# SingleEffect.net
KiCad netlist of a schematic drawn in EasyEDA Pro
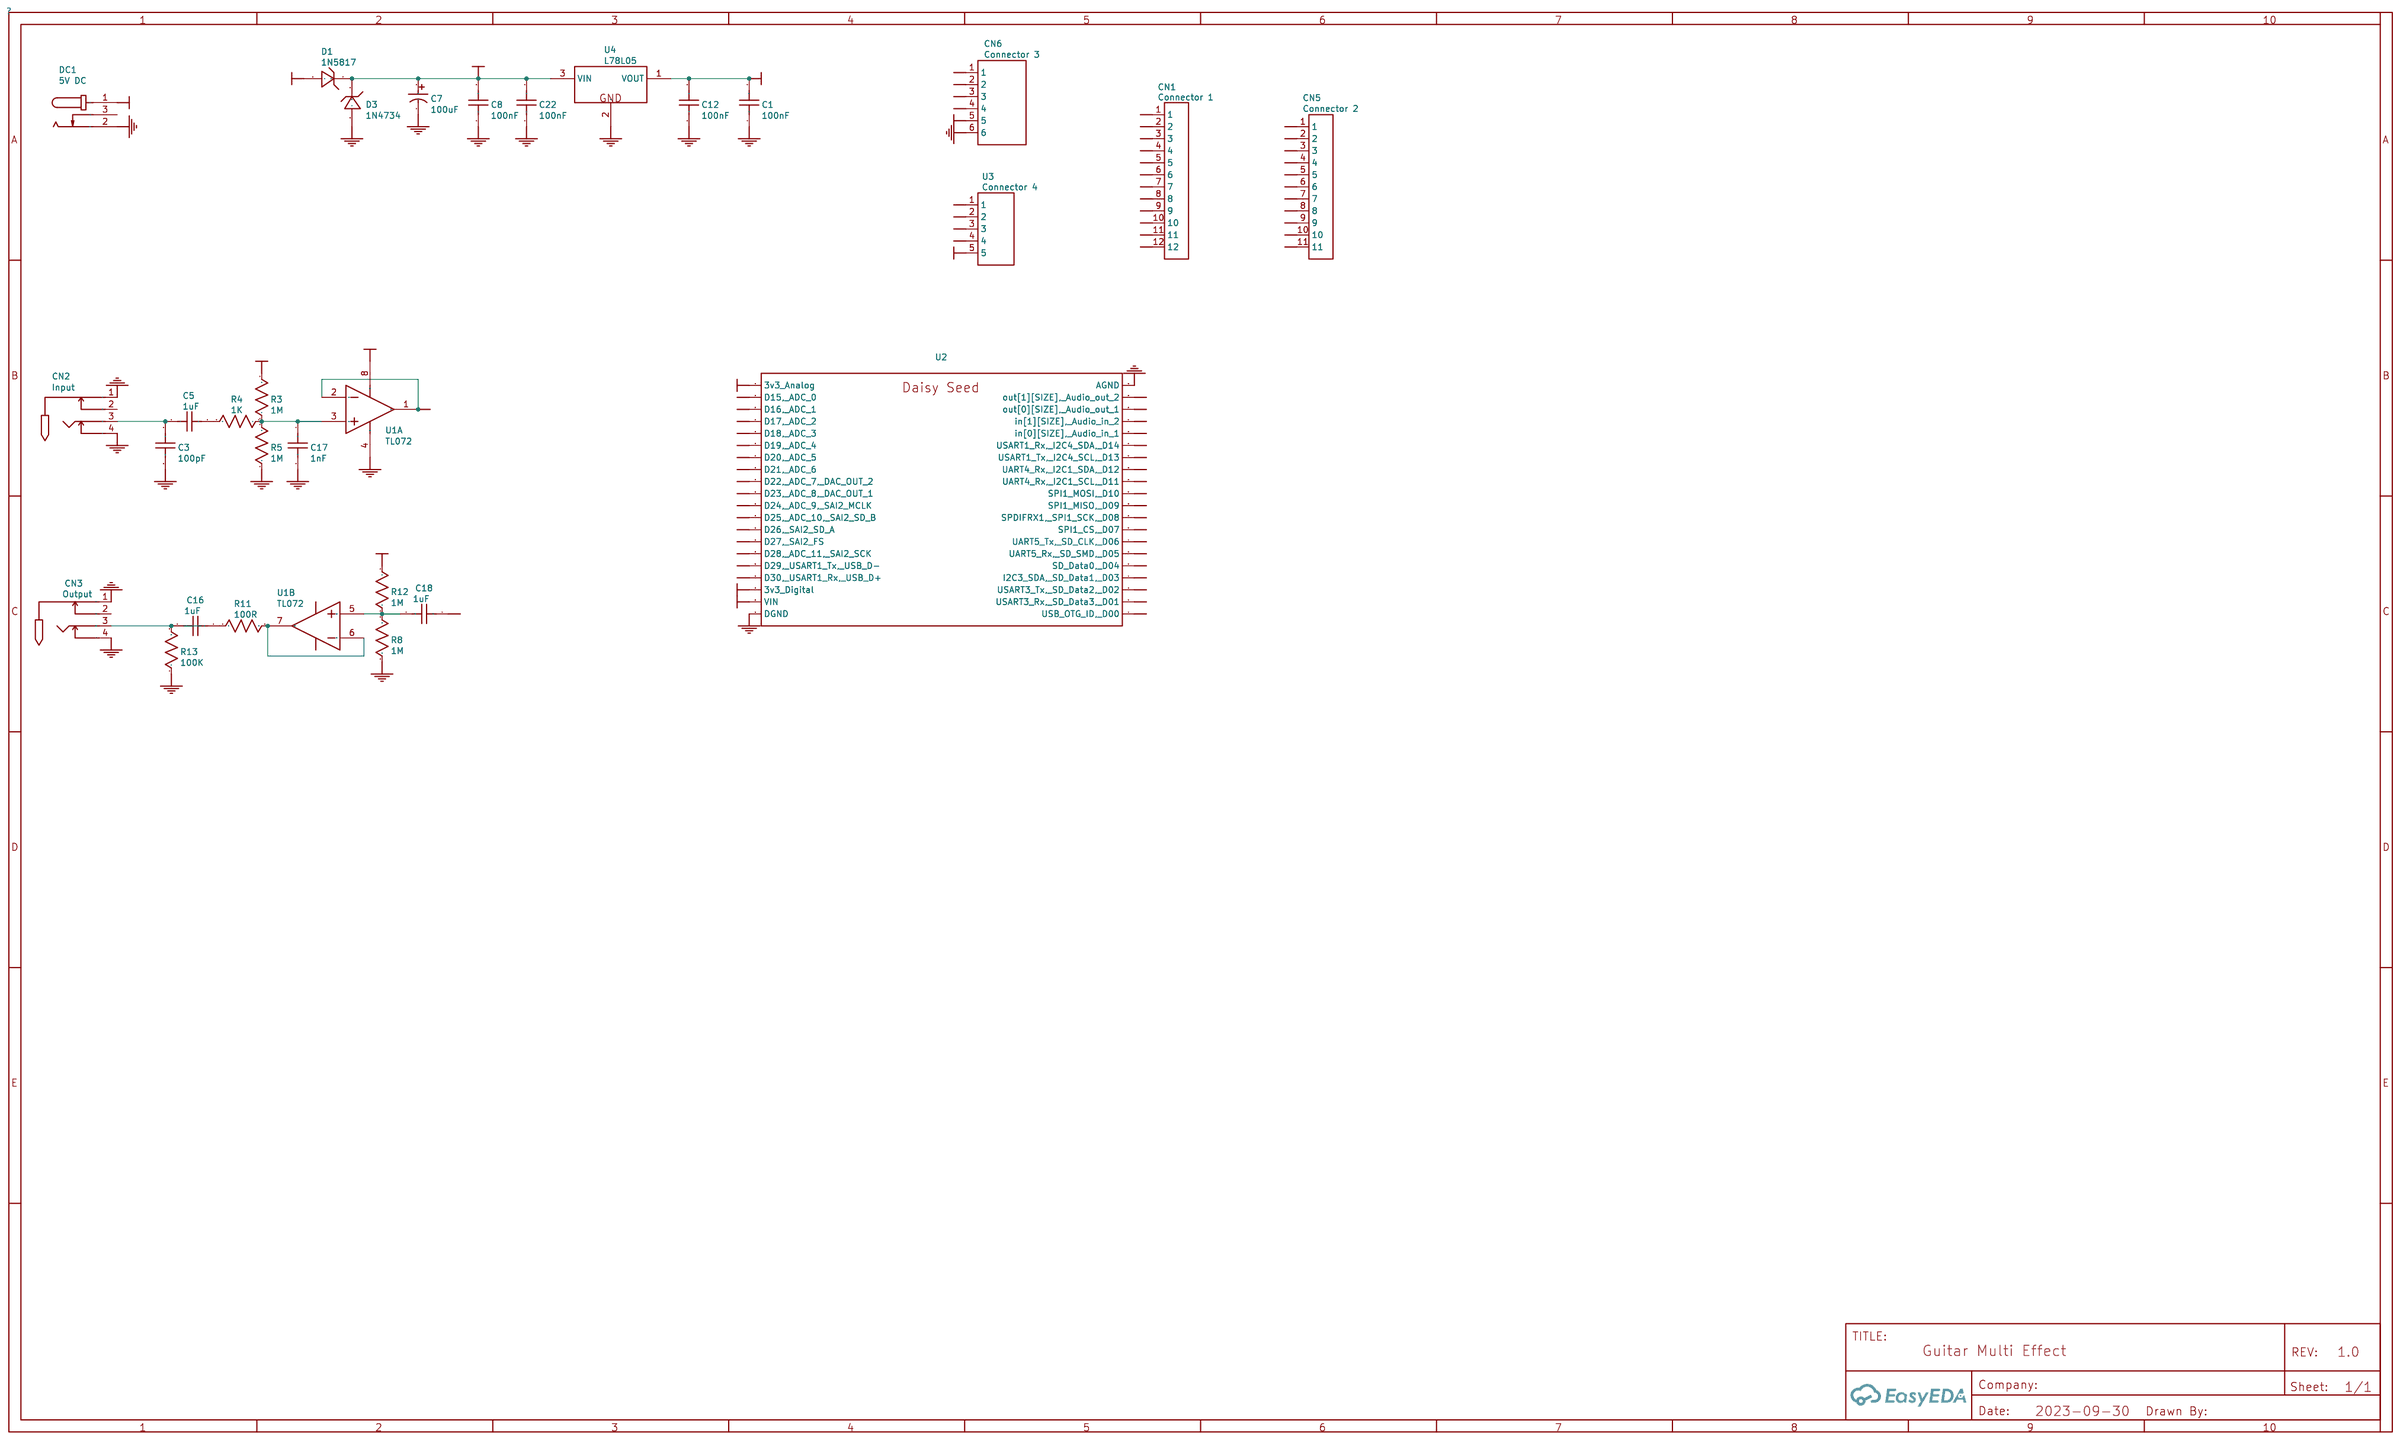
[diagram p0: schematic sheet]

(export (version "E")
  (design (tool "Eeschema 10.0.6"))
  (components
    (comp (ref "C1")
      (value "100nF")
      (footprint "easyedapro:CAP-TH_L8.0-W4.0-P5.00-D0.7")
      (fields
        (field (name "Manufacturer Part") "R08B1B102KN0B0S0N0")
        (field (name "Manufacturer") "STE(松田)")
        (field (name "Contributor") "LCSC")
      )
      (libsource (lib "easyedapro") (part "100nF"))
    )
    (comp (ref "C3")
      (value "100pF")
      (footprint "easyedapro:CAP-TH_L8.0-W4.0-P5.00-D0.7")
      (fields
        (field (name "Manufacturer Part") "R08B1B102KN0B0S0N0")
        (field (name "Manufacturer") "STE(松田)")
        (field (name "Contributor") "LCSC")
      )
      (libsource (lib "easyedapro") (part "100pF"))
    )
    (comp (ref "C5")
      (value "1uF")
      (footprint "easyedapro:CAP-TH_L8.0-W4.0-P5.00-D0.7")
      (fields
        (field (name "Manufacturer Part") "R08B1B102KN0B0S0N0")
        (field (name "Manufacturer") "STE(松田)")
        (field (name "Contributor") "LCSC")
      )
      (libsource (lib "easyedapro") (part "1uF"))
    )
    (comp (ref "C7")
      (value "100uF")
      (footprint "easyedapro:CAP-TH_BD5.0-P2.00-D0.8-FD")
      (fields
        (field (name "Manufacturer Part") "KM475M050D11RR0VH2FP0")
        (field (name "Manufacturer") "CX(承兴)")
      )
      (libsource (lib "easyedapro") (part "100uF"))
    )
    (comp (ref "C8")
      (value "100nF")
      (footprint "easyedapro:CAP-TH_L8.0-W4.0-P5.00-D0.7")
      (fields
        (field (name "Manufacturer Part") "R08B1B102KN0B0S0N0")
        (field (name "Manufacturer") "STE(松田)")
        (field (name "Contributor") "LCSC")
      )
      (libsource (lib "easyedapro") (part "100nF"))
    )
    (comp (ref "C12")
      (value "100nF")
      (footprint "easyedapro:CAP-TH_L8.0-W4.0-P5.00-D0.7")
      (fields
        (field (name "Manufacturer Part") "R08B1B102KN0B0S0N0")
        (field (name "Manufacturer") "STE(松田)")
        (field (name "Contributor") "LCSC")
      )
      (libsource (lib "easyedapro") (part "100nF"))
    )
    (comp (ref "C16")
      (value "1uF")
      (footprint "easyedapro:CAP-TH_L8.0-W4.0-P5.00-D0.7")
      (fields
        (field (name "Manufacturer Part") "R08B1B102KN0B0S0N0")
        (field (name "Manufacturer") "STE(松田)")
        (field (name "Contributor") "LCSC")
      )
      (libsource (lib "easyedapro") (part "1uF"))
    )
    (comp (ref "C17")
      (value "1nF")
      (footprint "easyedapro:CAP-TH_L8.0-W4.0-P5.00-D0.7")
      (fields
        (field (name "Manufacturer Part") "R08B1B102KN0B0S0N0")
        (field (name "Manufacturer") "STE(松田)")
        (field (name "Contributor") "LCSC")
      )
      (libsource (lib "easyedapro") (part "1nF"))
    )
    (comp (ref "C18")
      (value "1uF")
      (footprint "easyedapro:CAP-TH_L8.0-W4.0-P5.00-D0.7")
      (fields
        (field (name "Manufacturer Part") "R08B1B102KN0B0S0N0")
        (field (name "Manufacturer") "STE(松田)")
        (field (name "Contributor") "LCSC")
      )
      (libsource (lib "easyedapro") (part "1uF"))
    )
    (comp (ref "C22")
      (value "100nF")
      (footprint "easyedapro:CAP-TH_L8.0-W4.0-P5.00-D0.7")
      (fields
        (field (name "Manufacturer Part") "R08B1B102KN0B0S0N0")
        (field (name "Manufacturer") "STE(松田)")
        (field (name "Contributor") "LCSC")
      )
      (libsource (lib "easyedapro") (part "100nF"))
    )
    (comp (ref "CN1")
      (value "Connector 1")
      (footprint "easyedapro:CONN-TH_12P-P2.00_A2001WV-12P")
      (fields
        (field (name "Manufacturer Part") "A2001WV-12P")
        (field (name "Manufacturer") "CJT(长江连接器)")
        (field (name "Contributor") "LCSC")
      )
      (libsource (lib "easyedapro") (part "Connector 1"))
    )
    (comp (ref "CN2")
      (value "Input")
      (footprint "easyedapro:AUDIO-TH_CK6.35-3-15-6")
      (fields
        (field (name "Manufacturer Part") "CK6.35-3+15-6")
        (field (name "Manufacturer") "JINJIA(金佳)")
        (field (name "Contributor") "LCSC")
      )
      (libsource (lib "easyedapro") (part "Input"))
    )
    (comp (ref "CN3")
      (value "Output")
      (footprint "easyedapro:AUDIO-TH_CK6.35-3-15-6")
      (fields
        (field (name "Manufacturer Part") "CK6.35-3+15-6")
        (field (name "Manufacturer") "JINJIA(金佳)")
        (field (name "Contributor") "LCSC")
      )
      (libsource (lib "easyedapro") (part "Output"))
    )
    (comp (ref "CN5")
      (value "Connector 2")
      (footprint "easyedapro:CONN-TH_11P-P2.00_PH11A")
      (fields (field (name "Manufacturer Part") "PH-11A") (field (name "Manufacturer") "BOOMELE(博穆精密)"))
      (libsource (lib "easyedapro") (part "Connector 2"))
    )
    (comp (ref "CN6")
      (value "Connector 3")
      (footprint "easyedapro:CONN-TH_B06B-PASK-1-LF-SN")
      (fields
        (field (name "Manufacturer Part") "B06B-PASK-1(LF)(SN)")
        (field (name "Manufacturer") "JST")
        (field (name "Contributor") "LCSC")
      )
      (libsource (lib "easyedapro") (part "Connector 3"))
    )
    (comp (ref "D1")
      (value "1N5817")
      (footprint "easyedapro:DO-41_BD2.4-L4.7-P8.70-D0.9-RD")
      (fields (field (name "Manufacturer") "PINGWEI(平伟)") (field (name "Contributor") "LCSC"))
      (libsource (lib "easyedapro") (part "1N5817"))
    )
    (comp (ref "D3")
      (value "1N4734")
      (footprint "easyedapro:DO-41G_BD2.4-L4.0-P8.00-D0.7-RD")
      (fields
        (field (name "Manufacturer Part") "1N4734A-G_AY_10001")
        (field (name "Manufacturer") "PANJIT(强茂)")
        (field (name "Contributor") "LCSC")
      )
      (libsource (lib "easyedapro") (part "1N4734"))
    )
    (comp (ref "DC1")
      (value "5V DC")
      (footprint "easyedapro:CONN-TH_DC-005-2.5A-2.0")
      (fields
        (field (name "Manufacturer Part") "DC-005-2.5A-2.5")
        (field (name "Manufacturer") "XKB Connectivity(中国星坤)")
        (field (name "Contributor") "LCSC")
      )
      (libsource (lib "easyedapro") (part "5V DC"))
    )
    (comp (ref "R3")
      (value "1M")
      (footprint "easyedapro:PS-RES-16.5*6.42")
      (fields (field (name "Contributor") "LCEDA_Lib"))
      (libsource (lib "easyedapro") (part "1M"))
    )
    (comp (ref "R4")
      (value "1K")
      (footprint "easyedapro:PS-RES-16.5*6.42")
      (fields (field (name "Contributor") "LCEDA_Lib"))
      (libsource (lib "easyedapro") (part "1K"))
    )
    (comp (ref "R5")
      (value "1M")
      (footprint "easyedapro:PS-RES-16.5*6.42")
      (fields (field (name "Contributor") "LCEDA_Lib"))
      (libsource (lib "easyedapro") (part "1M"))
    )
    (comp (ref "R8")
      (value "1M")
      (footprint "easyedapro:PS-RES-16.5*6.42")
      (fields (field (name "Contributor") "LCEDA_Lib"))
      (libsource (lib "easyedapro") (part "1M"))
    )
    (comp (ref "R11")
      (value "100R")
      (footprint "easyedapro:PS-RES-16.5*6.42")
      (fields (field (name "Contributor") "LCEDA_Lib"))
      (libsource (lib "easyedapro") (part "100R"))
    )
    (comp (ref "R12")
      (value "1M")
      (footprint "easyedapro:PS-RES-16.5*6.42")
      (fields (field (name "Contributor") "LCEDA_Lib"))
      (libsource (lib "easyedapro") (part "1M"))
    )
    (comp (ref "R13")
      (value "100K")
      (footprint "easyedapro:PS-RES-16.5*6.42")
      (fields (field (name "Contributor") "LCEDA_Lib"))
      (libsource (lib "easyedapro") (part "100K"))
    )
    (comp (ref "U1")
      (value "TL072")
      (footprint "easyedapro:DIP-8_L9.7-W6.6-P2.54-LS7.6-BL")
      (fields (field (name "Manufacturer") "Gcore(扬州国芯)") (field (name "subpart_no") "1"))
      (libsource (lib "easyedapro") (part "TL072"))
    )
    (comp (ref "U2")
      (value "Daisy Seed")
      (footprint "easyedapro:DAISY_SEED")
      (fields (field (name "Contributor") "jjmens"))
      (libsource (lib "easyedapro") (part "Daisy Seed"))
    )
    (comp (ref "U3")
      (value "Connector 4")
      (footprint "easyedapro:CONN-TH_B5B-PH-K-S-LF-SN")
      (fields
        (field (name "Manufacturer Part") "B5B-PH-K-S(LF)(SN)")
        (field (name "Manufacturer") "JST")
        (field (name "Contributor") "LCSC")
      )
      (libsource (lib "easyedapro") (part "Connector 4"))
    )
    (comp (ref "U4")
      (value "L78L05")
      (footprint "easyedapro:TO-92-3_L4.9-W3.7-P1.27-L")
      (fields (field (name "Manufacturer Part") "L78L05ACZ") (field (name "Manufacturer") "ST(意法半导体)"))
      (libsource (lib "easyedapro") (part "L78L05"))
    )
  )
  (nets
    (net (code "1") (name "3V3A") (class "Default")
      (node (ref "CN6") (pin "5") (pinfunction "5_5") (pintype "unspecified"))
      (node (ref "U2") (pin "21") (pinfunction "3v3_Analog_21") (pintype "unspecified"))
    )
    (net (code "2") (name "3V3D") (class "Default")
      (node (ref "U2") (pin "38") (pinfunction "3v3_Digital_38") (pintype "unspecified"))
      (node (ref "U3") (pin "5") (pinfunction "5_5") (pintype "unspecified"))
    )
    (net (code "3") (name "5V") (class "Default")
      (node (ref "C1") (pin "2") (pinfunction "2_2") (pintype "unspecified"))
      (node (ref "C12") (pin "2") (pinfunction "2_2") (pintype "unspecified"))
      (node (ref "R12") (pin "2") (pinfunction "2_2") (pintype "unspecified"))
      (node (ref "R3") (pin "2") (pinfunction "2_2") (pintype "unspecified"))
      (node (ref "U1") (pin "8") (pinfunction "VCC+_8") (pintype "unspecified"))
      (node (ref "U4") (pin "1") (pinfunction "VOUT_1") (pintype "unspecified"))
    )
    (net (code "4") (name "5VDCIN") (class "Default")
      (node (ref "D1") (pin "2") (pinfunction "A_2") (pintype "unspecified"))
      (node (ref "DC1") (pin "1") (pinfunction "1_1") (pintype "unspecified"))
    )
    (net (code "5") (name "A00{slash}D15") (class "Default")
      (node (ref "CN1") (pin "1") (pinfunction "1_1") (pintype "unspecified"))
      (node (ref "U2") (pin "22") (pinfunction "D15,_ADC_0_22") (pintype "bidirectional"))
    )
    (net (code "6") (name "A01{slash}D16") (class "Default")
      (node (ref "CN1") (pin "2") (pinfunction "2_2") (pintype "unspecified"))
      (node (ref "U2") (pin "23") (pinfunction "D16,_ADC_1_23") (pintype "bidirectional"))
    )
    (net (code "7") (name "A02{slash}D17") (class "Default")
      (node (ref "CN1") (pin "3") (pinfunction "3_3") (pintype "unspecified"))
      (node (ref "U2") (pin "24") (pinfunction "D17,_ADC_2_24") (pintype "bidirectional"))
    )
    (net (code "8") (name "A03{slash}D18") (class "Default")
      (node (ref "CN1") (pin "4") (pinfunction "4_4") (pintype "unspecified"))
      (node (ref "U2") (pin "25") (pinfunction "D18,_ADC_3_25") (pintype "bidirectional"))
    )
    (net (code "9") (name "A04{slash}D19") (class "Default")
      (node (ref "CN1") (pin "5") (pinfunction "5_5") (pintype "unspecified"))
      (node (ref "U2") (pin "26") (pinfunction "D19,_ADC_4_26") (pintype "bidirectional"))
    )
    (net (code "10") (name "A05{slash}D20") (class "Default")
      (node (ref "CN1") (pin "6") (pinfunction "6_6") (pintype "unspecified"))
      (node (ref "U2") (pin "27") (pinfunction "D20,_ADC_5_27") (pintype "bidirectional"))
    )
    (net (code "11") (name "A06{slash}D21") (class "Default")
      (node (ref "CN1") (pin "7") (pinfunction "7_7") (pintype "unspecified"))
      (node (ref "U2") (pin "28") (pinfunction "D21,_ADC_6_28") (pintype "bidirectional"))
    )
    (net (code "12") (name "A07{slash}D22") (class "Default")
      (node (ref "CN1") (pin "8") (pinfunction "8_8") (pintype "unspecified"))
      (node (ref "U2") (pin "29") (pinfunction "D22,_ADC_7,_DAC_OUT_2_29") (pintype "bidirectional"))
    )
    (net (code "13") (name "A08{slash}D23") (class "Default")
      (node (ref "CN1") (pin "9") (pinfunction "9_9") (pintype "unspecified"))
      (node (ref "U2") (pin "30") (pinfunction "D23,_ADC_8,_DAC_OUT_1_30") (pintype "bidirectional"))
    )
    (net (code "14") (name "A09{slash}D24") (class "Default")
      (node (ref "CN1") (pin "10") (pinfunction "10_10") (pintype "unspecified"))
      (node (ref "U2") (pin "31") (pinfunction "D24,_ADC_9,_SAI2_MCLK_31") (pintype "bidirectional"))
    )
    (net (code "15") (name "A10{slash}D25") (class "Default")
      (node (ref "CN1") (pin "11") (pinfunction "11_11") (pintype "unspecified"))
      (node (ref "U2") (pin "32") (pinfunction "D25,_ADC_10,_SAI2_SD_B_32") (pintype "bidirectional"))
    )
    (net (code "16") (name "A11{slash}D28") (class "Default")
      (node (ref "CN1") (pin "12") (pinfunction "12_12") (pintype "unspecified"))
      (node (ref "U2") (pin "35") (pinfunction "D28,_ADC_11,_SAI2_SCK_35") (pintype "bidirectional"))
    )
    (net (code "17") (name "D00") (class "Default")
      (node (ref "CN5") (pin "1") (pinfunction "1_1") (pintype "unspecified"))
      (node (ref "U2") (pin "1") (pinfunction "USB_OTG_ID,_D00_1") (pintype "bidirectional"))
    )
    (net (code "18") (name "D01") (class "Default")
      (node (ref "CN5") (pin "2") (pinfunction "2_2") (pintype "unspecified"))
      (node (ref "U2") (pin "2") (pinfunction "USART3_Rx,_SD_Data3,_D01_2") (pintype "bidirectional"))
    )
    (net (code "19") (name "D02") (class "Default")
      (node (ref "CN5") (pin "3") (pinfunction "3_3") (pintype "unspecified"))
      (node (ref "U2") (pin "3") (pinfunction "USART3_Tx,_SD_Data2,_D02_3") (pintype "bidirectional"))
    )
    (net (code "20") (name "D03") (class "Default")
      (node (ref "CN5") (pin "4") (pinfunction "4_4") (pintype "unspecified"))
      (node (ref "U2") (pin "4") (pinfunction "I2C3_SDA,_SD_Data1,_D03_4") (pintype "bidirectional"))
    )
    (net (code "21") (name "D04") (class "Default")
      (node (ref "CN5") (pin "5") (pinfunction "5_5") (pintype "unspecified"))
      (node (ref "U2") (pin "5") (pinfunction "SD_Data0,_D04_5") (pintype "bidirectional"))
    )
    (net (code "22") (name "D05") (class "Default")
      (node (ref "CN5") (pin "6") (pinfunction "6_6") (pintype "unspecified"))
      (node (ref "U2") (pin "6") (pinfunction "UART5_Rx,_SD_SMD,_D05_6") (pintype "bidirectional"))
    )
    (net (code "23") (name "D06") (class "Default")
      (node (ref "CN5") (pin "7") (pinfunction "7_7") (pintype "unspecified"))
      (node (ref "U2") (pin "7") (pinfunction "UART5_Tx,_SD_CLK,_D06_7") (pintype "bidirectional"))
    )
    (net (code "24") (name "D07") (class "Default")
      (node (ref "CN5") (pin "8") (pinfunction "8_8") (pintype "unspecified"))
      (node (ref "U2") (pin "8") (pinfunction "SPI1_CS,_D07_8") (pintype "bidirectional"))
    )
    (net (code "25") (name "D08") (class "Default")
      (node (ref "CN5") (pin "9") (pinfunction "9_9") (pintype "unspecified"))
      (node (ref "U2") (pin "9") (pinfunction "SPDIFRX1,_SPI1_SCK,_D08_9") (pintype "bidirectional"))
    )
    (net (code "26") (name "D09") (class "Default")
      (node (ref "CN5") (pin "10") (pinfunction "10_10") (pintype "unspecified"))
      (node (ref "U2") (pin "10") (pinfunction "SPI1_MISO,_D09_10") (pintype "bidirectional"))
    )
    (net (code "27") (name "D10") (class "Default")
      (node (ref "CN5") (pin "11") (pinfunction "11_11") (pintype "unspecified"))
      (node (ref "U2") (pin "11") (pinfunction "SPI1_MOSI,_D10_11") (pintype "bidirectional"))
    )
    (net (code "28") (name "D11") (class "Default")
      (node (ref "CN6") (pin "1") (pinfunction "1_1") (pintype "unspecified"))
      (node (ref "U2") (pin "12") (pinfunction "UART4_Rx,_I2C1_SCL,_D11_12") (pintype "bidirectional"))
    )
    (net (code "29") (name "D12") (class "Default")
      (node (ref "CN6") (pin "2") (pinfunction "2_2") (pintype "unspecified"))
      (node (ref "U2") (pin "13") (pinfunction "UART4_Rx,_I2C1_SDA,_D12_13") (pintype "bidirectional"))
    )
    (net (code "30") (name "D13") (class "Default")
      (node (ref "CN6") (pin "3") (pinfunction "3_3") (pintype "unspecified"))
      (node (ref "U2") (pin "14") (pinfunction "USART1_Tx,_I2C4_SCL,_D13_14") (pintype "bidirectional"))
    )
    (net (code "31") (name "D14") (class "Default")
      (node (ref "CN6") (pin "4") (pinfunction "4_4") (pintype "unspecified"))
      (node (ref "U2") (pin "15") (pinfunction "USART1_Rx,_I2C4_SDA,_D14_15") (pintype "bidirectional"))
    )
    (net (code "32") (name "D26") (class "Default")
      (node (ref "U2") (pin "33") (pinfunction "D26,_SAI2_SD_A_33") (pintype "bidirectional"))
      (node (ref "U3") (pin "1") (pinfunction "1_1") (pintype "unspecified"))
    )
    (net (code "33") (name "D27") (class "Default")
      (node (ref "U2") (pin "34") (pinfunction "D27,_SAI2_FS_34") (pintype "bidirectional"))
      (node (ref "U3") (pin "2") (pinfunction "2_2") (pintype "unspecified"))
    )
    (net (code "34") (name "D29") (class "Default")
      (node (ref "U2") (pin "36") (pinfunction "D29,_USART1_Tx,_USB_D-_36") (pintype "bidirectional"))
      (node (ref "U3") (pin "3") (pinfunction "3_3") (pintype "unspecified"))
    )
    (net (code "35") (name "D30") (class "Default")
      (node (ref "U2") (pin "37") (pinfunction "D30,_USART1_Rx,_USB_D+_37") (pintype "bidirectional"))
      (node (ref "U3") (pin "4") (pinfunction "4_4") (pintype "unspecified"))
    )
    (net (code "36") (name "GND") (class "Default")
      (node (ref "C1") (pin "1") (pinfunction "1_1") (pintype "unspecified"))
      (node (ref "C12") (pin "1") (pinfunction "1_1") (pintype "unspecified"))
      (node (ref "C17") (pin "2") (pinfunction "2_2") (pintype "unspecified"))
      (node (ref "C22") (pin "1") (pinfunction "1_1") (pintype "unspecified"))
      (node (ref "C3") (pin "2") (pinfunction "2_2") (pintype "unspecified"))
      (node (ref "C7") (pin "2") (pinfunction "2_2") (pintype "input"))
      (node (ref "C8") (pin "1") (pinfunction "1_1") (pintype "unspecified"))
      (node (ref "CN2") (pin "1") (pinfunction "1_1") (pintype "input"))
      (node (ref "CN2") (pin "4") (pinfunction "4_4") (pintype "input"))
      (node (ref "CN3") (pin "1") (pinfunction "1_1") (pintype "input"))
      (node (ref "CN3") (pin "4") (pinfunction "4_4") (pintype "input"))
      (node (ref "CN6") (pin "6") (pinfunction "6_6") (pintype "unspecified"))
      (node (ref "D3") (pin "2") (pinfunction "A_2") (pintype "unspecified"))
      (node (ref "DC1") (pin "2") (pinfunction "2_2") (pintype "unspecified"))
      (node (ref "R13") (pin "1") (pinfunction "1_1") (pintype "unspecified"))
      (node (ref "R5") (pin "1") (pinfunction "1_1") (pintype "unspecified"))
      (node (ref "R8") (pin "1") (pinfunction "1_1") (pintype "unspecified"))
      (node (ref "U1") (pin "4") (pinfunction "VCC-_4") (pintype "unspecified"))
      (node (ref "U2") (pin "20") (pinfunction "AGND_20") (pintype "unspecified"))
      (node (ref "U2") (pin "40") (pinfunction "DGND_40") (pintype "unspecified"))
      (node (ref "U4") (pin "2") (pinfunction "GND_2") (pintype "unspecified"))
    )
    (net (code "37") (name "LINEINL") (class "Default")
      (node (ref "U1") (pin "1") (pinfunction "1OUT_1") (pintype "output"))
      (node (ref "U1") (pin "2") (pinfunction "1IN-_2") (pintype "unspecified"))
      (node (ref "U2") (pin "16") (pinfunction "in[0][SIZE],_Audio_in_1_16") (pintype "input"))
    )
    (net (code "38") (name "LINEINR") (class "Default")
      (node (ref "U2") (pin "17") (pinfunction "in[1][SIZE],_Audio_in_2_17") (pintype "input"))
    )
    (net (code "39") (name "LINEOUTL") (class "Default")
      (node (ref "C18") (pin "1") (pinfunction "1_1") (pintype "unspecified"))
      (node (ref "U2") (pin "18") (pinfunction "out[0][SIZE],_Audio_out_1_18") (pintype "output"))
    )
    (net (code "40") (name "LINEOUTR") (class "Default")
      (node (ref "U2") (pin "19") (pinfunction "out[1][SIZE],_Audio_out_2_19") (pintype "output"))
    )
    (net (code "41") (name "Net-(C3-Pad1)") (class "Default")
      (node (ref "C3") (pin "1") (pinfunction "1_1") (pintype "unspecified"))
      (node (ref "C5") (pin "1") (pinfunction "1_1") (pintype "unspecified"))
      (node (ref "CN2") (pin "3") (pinfunction "3_3") (pintype "input"))
    )
    (net (code "42") (name "Net-(C5-Pad2)") (class "Default")
      (node (ref "C5") (pin "2") (pinfunction "2_2") (pintype "unspecified"))
      (node (ref "R4") (pin "2") (pinfunction "2_2") (pintype "unspecified"))
    )
    (net (code "43") (name "Net-(C16-Pad1)") (class "Default")
      (node (ref "C16") (pin "1") (pinfunction "1_1") (pintype "unspecified"))
      (node (ref "R11") (pin "1") (pinfunction "1_1") (pintype "unspecified"))
    )
    (net (code "44") (name "Net-(C16-Pad2)") (class "Default")
      (node (ref "C16") (pin "2") (pinfunction "2_2") (pintype "unspecified"))
      (node (ref "CN3") (pin "3") (pinfunction "3_3") (pintype "input"))
      (node (ref "R13") (pin "2") (pinfunction "2_2") (pintype "unspecified"))
    )
    (net (code "45") (name "Net-(U1A-1IN+)") (class "Default")
      (node (ref "C17") (pin "1") (pinfunction "1_1") (pintype "unspecified"))
      (node (ref "R3") (pin "1") (pinfunction "1_1") (pintype "unspecified"))
      (node (ref "R4") (pin "1") (pinfunction "1_1") (pintype "unspecified"))
      (node (ref "R5") (pin "2") (pinfunction "2_2") (pintype "unspecified"))
      (node (ref "U1") (pin "3") (pinfunction "1IN+_3") (pintype "unspecified"))
    )
    (net (code "46") (name "Net-(U1B-2IN+)") (class "Default")
      (node (ref "C18") (pin "2") (pinfunction "2_2") (pintype "unspecified"))
      (node (ref "R12") (pin "1") (pinfunction "1_1") (pintype "unspecified"))
      (node (ref "R8") (pin "2") (pinfunction "2_2") (pintype "unspecified"))
      (node (ref "U1") (pin "5") (pinfunction "2IN+_5") (pintype "unspecified"))
    )
    (net (code "47") (name "Net-(U1B-2IN-)") (class "Default")
      (node (ref "R11") (pin "2") (pinfunction "2_2") (pintype "unspecified"))
      (node (ref "U1") (pin "6") (pinfunction "2IN-_6") (pintype "unspecified"))
      (node (ref "U1") (pin "7") (pinfunction "2OUT_7") (pintype "output"))
    )
    (net (code "48") (name "VCC") (class "Default")
      (node (ref "C22") (pin "2") (pinfunction "2_2") (pintype "unspecified"))
      (node (ref "C7") (pin "1") (pinfunction "1_1") (pintype "input"))
      (node (ref "C8") (pin "2") (pinfunction "2_2") (pintype "unspecified"))
      (node (ref "D1") (pin "1") (pinfunction "C_1") (pintype "unspecified"))
      (node (ref "D3") (pin "1") (pinfunction "C_1") (pintype "unspecified"))
      (node (ref "U2") (pin "39") (pinfunction "VIN_39") (pintype "unspecified"))
      (node (ref "U4") (pin "3") (pinfunction "VIN_3") (pintype "unspecified"))
    )
    (net (code "49") (name "unconnected-(CN2-Pad2)") (class "Default")
      (node (ref "CN2") (pin "2") (pinfunction "2_2") (pintype "input"))
    )
    (net (code "50") (name "unconnected-(CN3-Pad2)") (class "Default")
      (node (ref "CN3") (pin "2") (pinfunction "2_2") (pintype "input"))
    )
    (net (code "51") (name "unconnected-(DC1-Pad3)") (class "Default")
      (node (ref "DC1") (pin "3") (pinfunction "3_3") (pintype "unspecified"))
    )
  )
)
